# Pcb_desigin.net
KiCad netlist of a schematic drawn in EAGLE
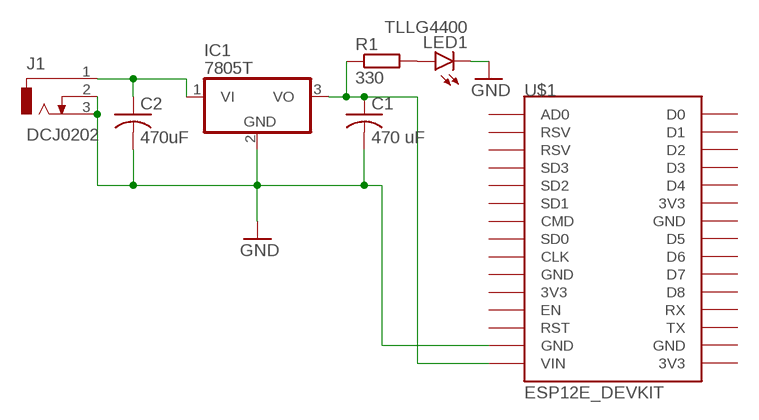
[diagram p0: schematic, sheet 1]

(export (version "E")
  (design (tool "Eeschema 10.0.6"))
  (components
    (comp (ref "C1")
      (value "470 uF")
      (footprint "eagle-import:C025-025X050")
      (libsource (lib "eagle-import") (part "C-US025-025X050"))
    )
    (comp (ref "C2")
      (value "470uF")
      (footprint "eagle-import:C025-025X050")
      (libsource (lib "eagle-import") (part "C-US025-025X050"))
    )
    (comp (ref "IC1")
      (value "7805T")
      (footprint "eagle-import:TO220H")
      (libsource (lib "eagle-import") (part "78T05"))
    )
    (comp (ref "J1")
      (value "DCJ0202")
      (footprint "eagle-import:DCJ0202")
      (libsource (lib "eagle-import") (part "DCJ0202"))
    )
    (comp (ref "LED1")
      (value "TLLG4400")
      (footprint "eagle-import:LED3MM")
      (fields (field (name "MF") "VISHAY SEMICONDUCTOR"))
      (libsource (lib "eagle-import") (part "TLLG4400"))
    )
    (comp (ref "R1")
      (value "330")
      (footprint "eagle-import:RDH_15")
      (libsource (lib "eagle-import") (part "R-EU_RDH/15"))
    )
    (comp (ref "U$1")
      (value "ESP12E_DEVKIT")
      (footprint "eagle-import:ESP12E_DEVKIT")
      (libsource (lib "eagle-import") (part "ESP12E_DEVKIT"))
    )
  )
  (nets
    (net (code "1") (name "GND") (class "Default")
      (node (ref "C1") (pin "2") (pinfunction "2_2") (pintype "passive"))
      (node (ref "C2") (pin "2") (pinfunction "2_2") (pintype "passive"))
      (node (ref "IC1") (pin "2") (pinfunction "GND_2") (pintype "passive"))
      (node (ref "J1") (pin "2") (pinfunction "2_2") (pintype "passive"))
      (node (ref "J1") (pin "3") (pinfunction "3_3") (pintype "passive"))
      (node (ref "LED1") (pin "K") (pinfunction "C_K") (pintype "passive"))
      (node (ref "U$1") (pin "GND@1") (pinfunction "GND_GND@1") (pintype "bidirectional"))
    )
    (net (code "2") (name "Net-(IC1-VI)") (class "Default")
      (node (ref "C2") (pin "1") (pinfunction "1_1") (pintype "passive"))
      (node (ref "IC1") (pin "1") (pinfunction "VI_1") (pintype "input"))
      (node (ref "J1") (pin "1") (pinfunction "1_1") (pintype "passive"))
    )
    (net (code "3") (name "Net-(IC1-VO)") (class "Default")
      (node (ref "C1") (pin "1") (pinfunction "1_1") (pintype "passive"))
      (node (ref "IC1") (pin "3") (pinfunction "VO_3") (pintype "passive"))
      (node (ref "R1") (pin "1") (pinfunction "1_1") (pintype "passive"))
      (node (ref "U$1") (pin "VIN") (pinfunction "VIN_VIN") (pintype "bidirectional"))
    )
    (net (code "4") (name "Net-(LED1-PadA)") (class "Default")
      (node (ref "LED1") (pin "A") (pinfunction "A_A") (pintype "passive"))
      (node (ref "R1") (pin "2") (pinfunction "2_2") (pintype "passive"))
    )
    (net (code "5") (name "unconnected-(U$1-3V3-Pad3V3@0)") (class "Default")
      (node (ref "U$1") (pin "3V3@0") (pinfunction "3V3_3V3@0") (pintype "bidirectional"))
    )
    (net (code "6") (name "unconnected-(U$1-3V3-Pad3V3@1)") (class "Default")
      (node (ref "U$1") (pin "3V3@1") (pinfunction "3V3_3V3@1") (pintype "bidirectional"))
    )
    (net (code "7") (name "unconnected-(U$1-3V3-Pad3V3@2)") (class "Default")
      (node (ref "U$1") (pin "3V3@2") (pinfunction "3V3_3V3@2") (pintype "bidirectional"))
    )
    (net (code "8") (name "unconnected-(U$1-GND-PadGND@0)") (class "Default")
      (node (ref "U$1") (pin "GND@0") (pinfunction "GND_GND@0") (pintype "bidirectional"))
    )
    (net (code "9") (name "unconnected-(U$1-GND-PadGND@2)") (class "Default")
      (node (ref "U$1") (pin "GND@2") (pinfunction "GND_GND@2") (pintype "bidirectional"))
    )
    (net (code "10") (name "unconnected-(U$1-GND-PadGND@3)") (class "Default")
      (node (ref "U$1") (pin "GND@3") (pinfunction "GND_GND@3") (pintype "bidirectional"))
    )
    (net (code "11") (name "unconnected-(U$1-PadAD0)") (class "Default")
      (node (ref "U$1") (pin "AD0") (pinfunction "AD0_AD0") (pintype "bidirectional"))
    )
    (net (code "12") (name "unconnected-(U$1-PadCLK)") (class "Default")
      (node (ref "U$1") (pin "CLK") (pinfunction "CLK_CLK") (pintype "bidirectional"))
    )
    (net (code "13") (name "unconnected-(U$1-PadCMD)") (class "Default")
      (node (ref "U$1") (pin "CMD") (pinfunction "CMD_CMD") (pintype "bidirectional"))
    )
    (net (code "14") (name "unconnected-(U$1-PadD0)") (class "Default")
      (node (ref "U$1") (pin "D0") (pinfunction "D0_D0") (pintype "bidirectional"))
    )
    (net (code "15") (name "unconnected-(U$1-PadD1)") (class "Default")
      (node (ref "U$1") (pin "D1") (pinfunction "D1_D1") (pintype "bidirectional"))
    )
    (net (code "16") (name "unconnected-(U$1-PadD2)") (class "Default")
      (node (ref "U$1") (pin "D2") (pinfunction "D2_D2") (pintype "bidirectional"))
    )
    (net (code "17") (name "unconnected-(U$1-PadD3)") (class "Default")
      (node (ref "U$1") (pin "D3") (pinfunction "D3_D3") (pintype "bidirectional"))
    )
    (net (code "18") (name "unconnected-(U$1-PadD4)") (class "Default")
      (node (ref "U$1") (pin "D4") (pinfunction "D4_D4") (pintype "bidirectional"))
    )
    (net (code "19") (name "unconnected-(U$1-PadD5)") (class "Default")
      (node (ref "U$1") (pin "D5") (pinfunction "D5_D5") (pintype "bidirectional"))
    )
    (net (code "20") (name "unconnected-(U$1-PadD6)") (class "Default")
      (node (ref "U$1") (pin "D6") (pinfunction "D6_D6") (pintype "bidirectional"))
    )
    (net (code "21") (name "unconnected-(U$1-PadD7)") (class "Default")
      (node (ref "U$1") (pin "D7") (pinfunction "D7_D7") (pintype "bidirectional"))
    )
    (net (code "22") (name "unconnected-(U$1-PadD8)") (class "Default")
      (node (ref "U$1") (pin "D8") (pinfunction "D8_D8") (pintype "bidirectional"))
    )
    (net (code "23") (name "unconnected-(U$1-PadEN)") (class "Default")
      (node (ref "U$1") (pin "EN") (pinfunction "EN_EN") (pintype "bidirectional"))
    )
    (net (code "24") (name "unconnected-(U$1-PadRST)") (class "Default")
      (node (ref "U$1") (pin "RST") (pinfunction "RST_RST") (pintype "bidirectional"))
    )
    (net (code "25") (name "unconnected-(U$1-PadRX)") (class "Default")
      (node (ref "U$1") (pin "RX") (pinfunction "RX_RX") (pintype "bidirectional"))
    )
    (net (code "26") (name "unconnected-(U$1-PadSD0)") (class "Default")
      (node (ref "U$1") (pin "SD0") (pinfunction "SD0_SD0") (pintype "bidirectional"))
    )
    (net (code "27") (name "unconnected-(U$1-PadSD1)") (class "Default")
      (node (ref "U$1") (pin "SD1") (pinfunction "SD1_SD1") (pintype "bidirectional"))
    )
    (net (code "28") (name "unconnected-(U$1-PadSD2)") (class "Default")
      (node (ref "U$1") (pin "SD2") (pinfunction "SD2_SD2") (pintype "bidirectional"))
    )
    (net (code "29") (name "unconnected-(U$1-PadSD3)") (class "Default")
      (node (ref "U$1") (pin "SD3") (pinfunction "SD3_SD3") (pintype "bidirectional"))
    )
    (net (code "30") (name "unconnected-(U$1-PadTX)") (class "Default")
      (node (ref "U$1") (pin "TX") (pinfunction "TX_TX") (pintype "bidirectional"))
    )
    (net (code "31") (name "unconnected-(U$1-RSV-PadRSV@0)") (class "Default")
      (node (ref "U$1") (pin "RSV@0") (pinfunction "RSV_RSV@0") (pintype "bidirectional"))
    )
    (net (code "32") (name "unconnected-(U$1-RSV-PadRSV@1)") (class "Default")
      (node (ref "U$1") (pin "RSV@1") (pinfunction "RSV_RSV@1") (pintype "bidirectional"))
    )
  )
)
